# 1010-B1-solarwhat-light.net
KiCad netlist of a schematic drawn in EAGLE
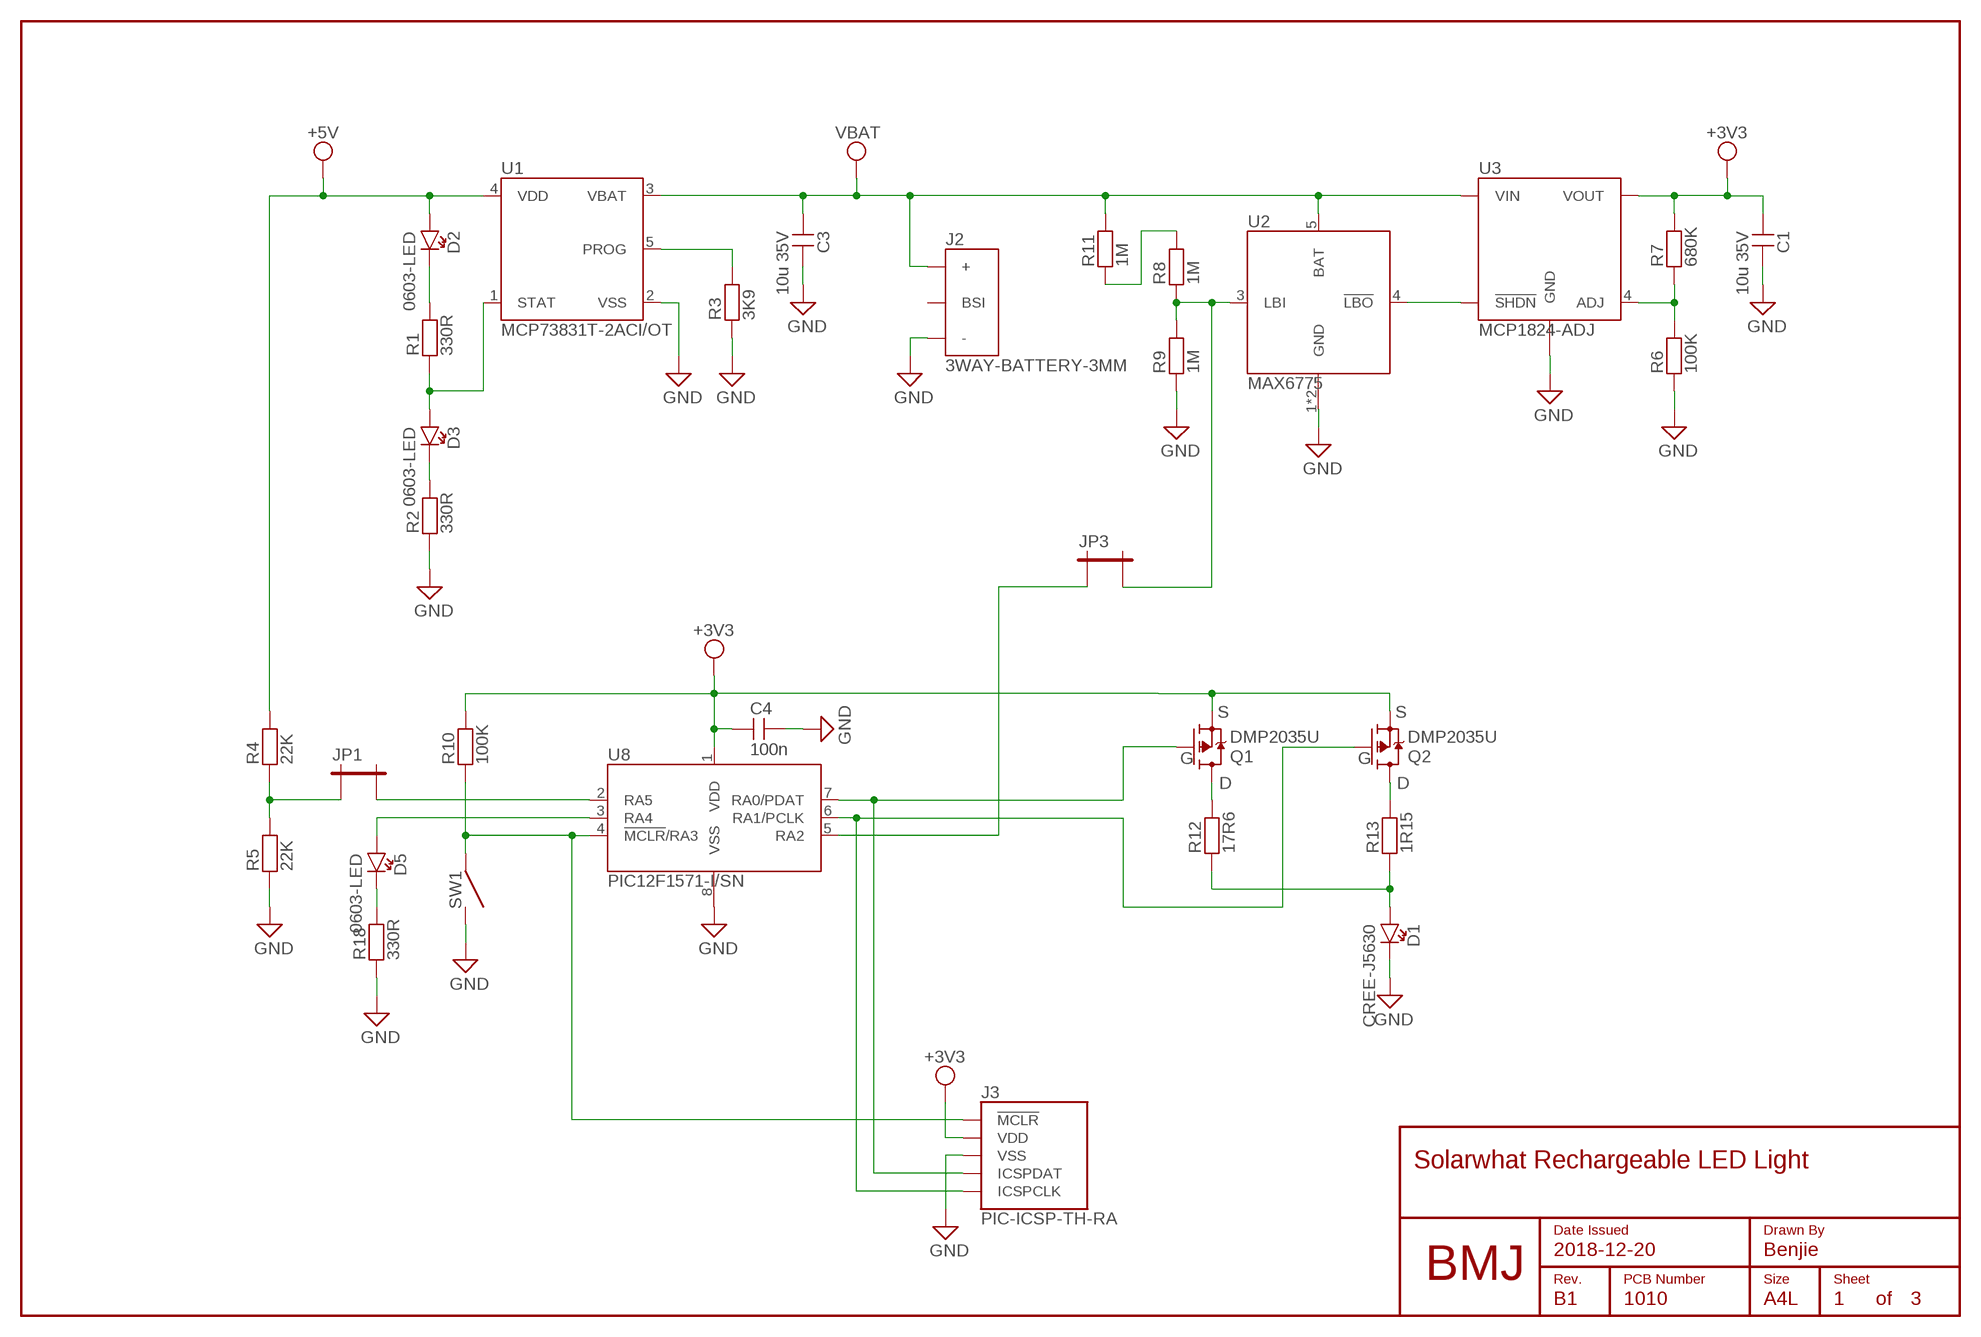
[diagram p0: schematic, sheet 1]
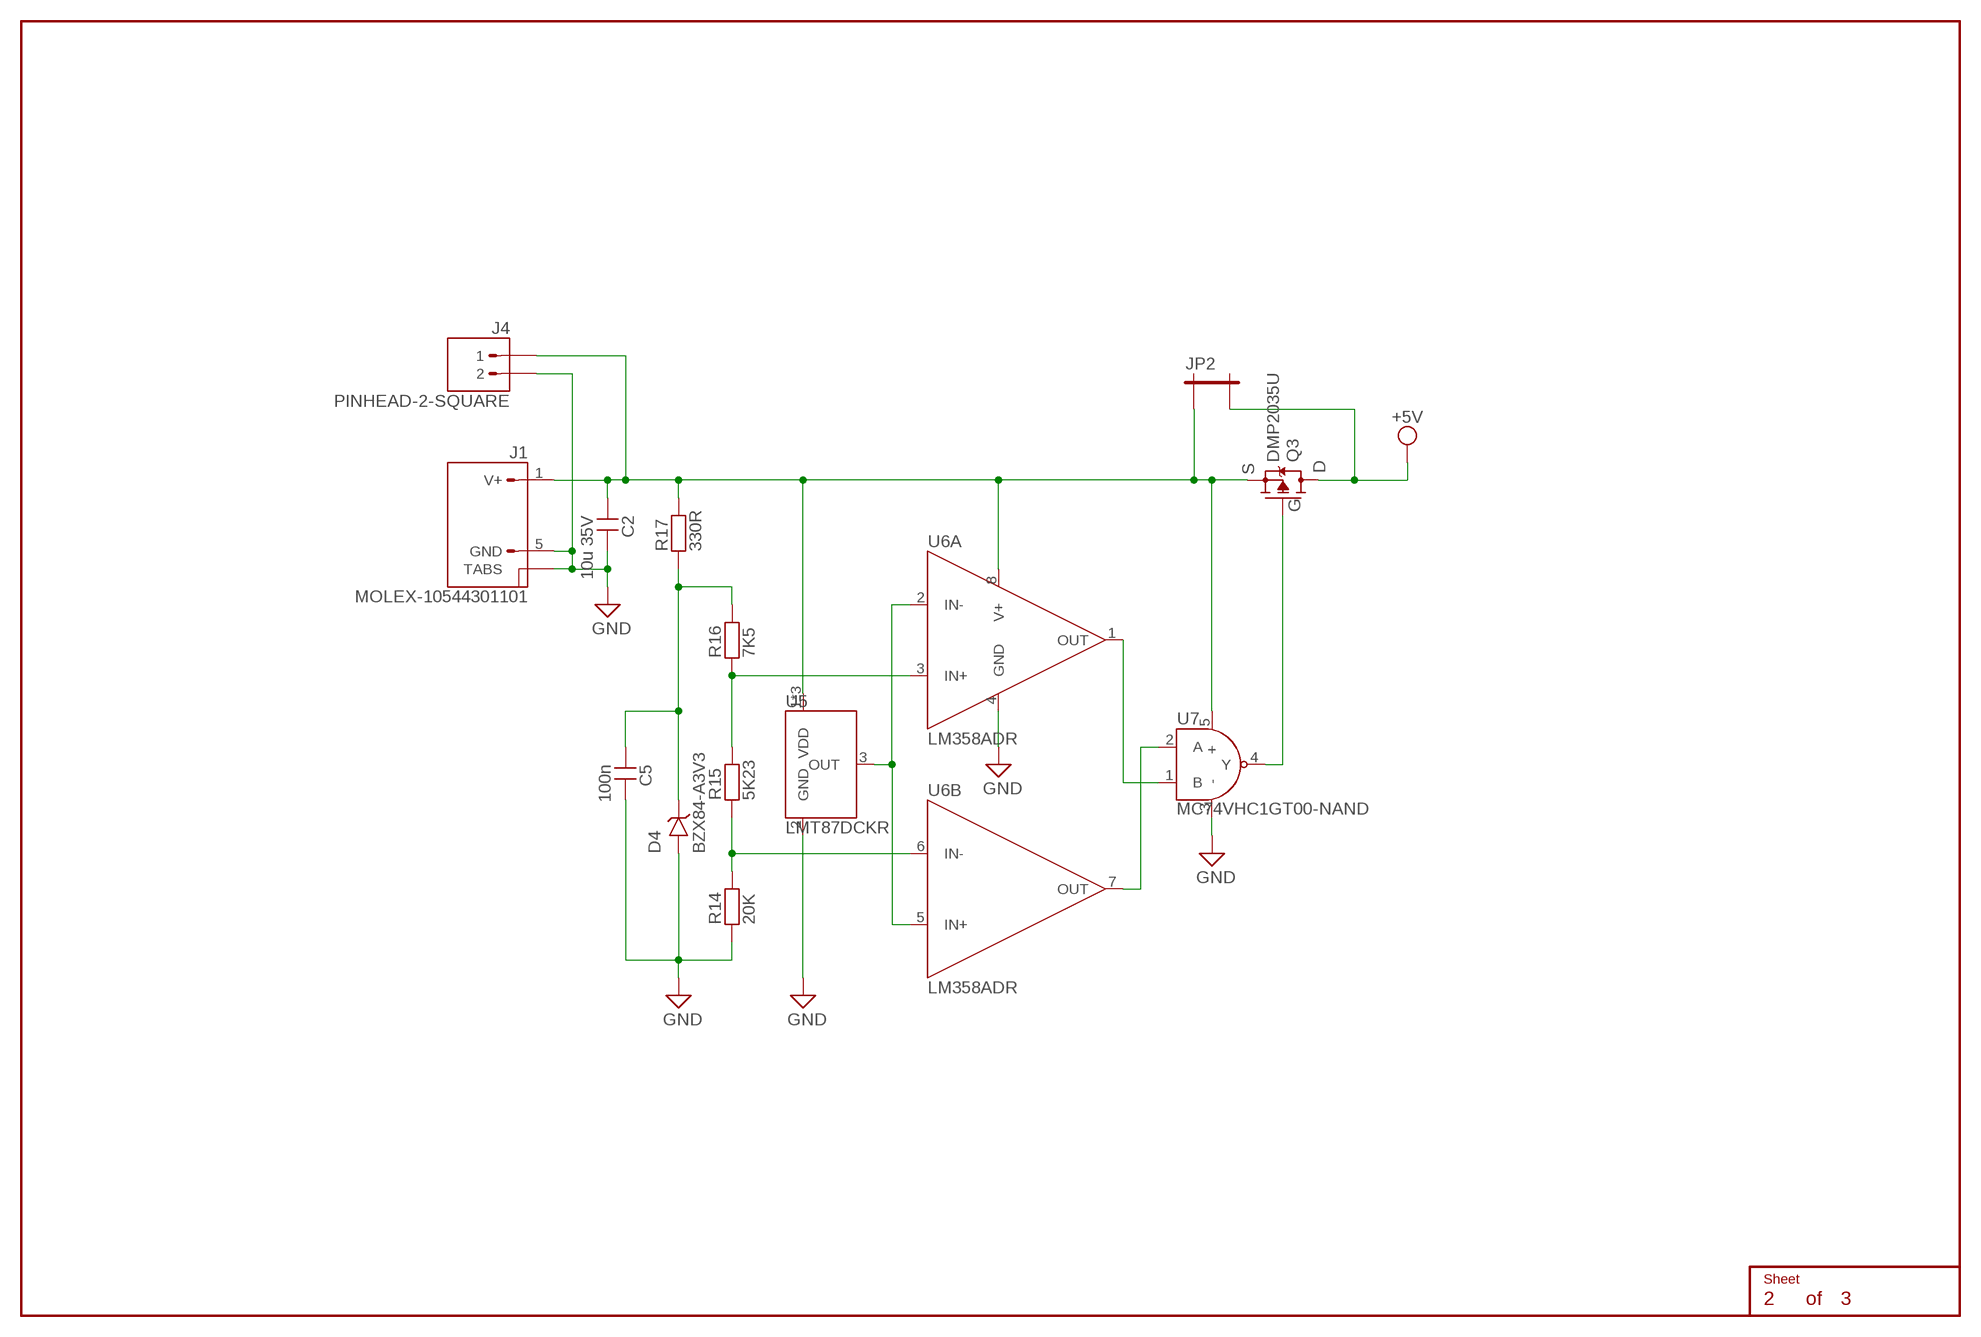
[diagram p1: schematic, sheet 2]
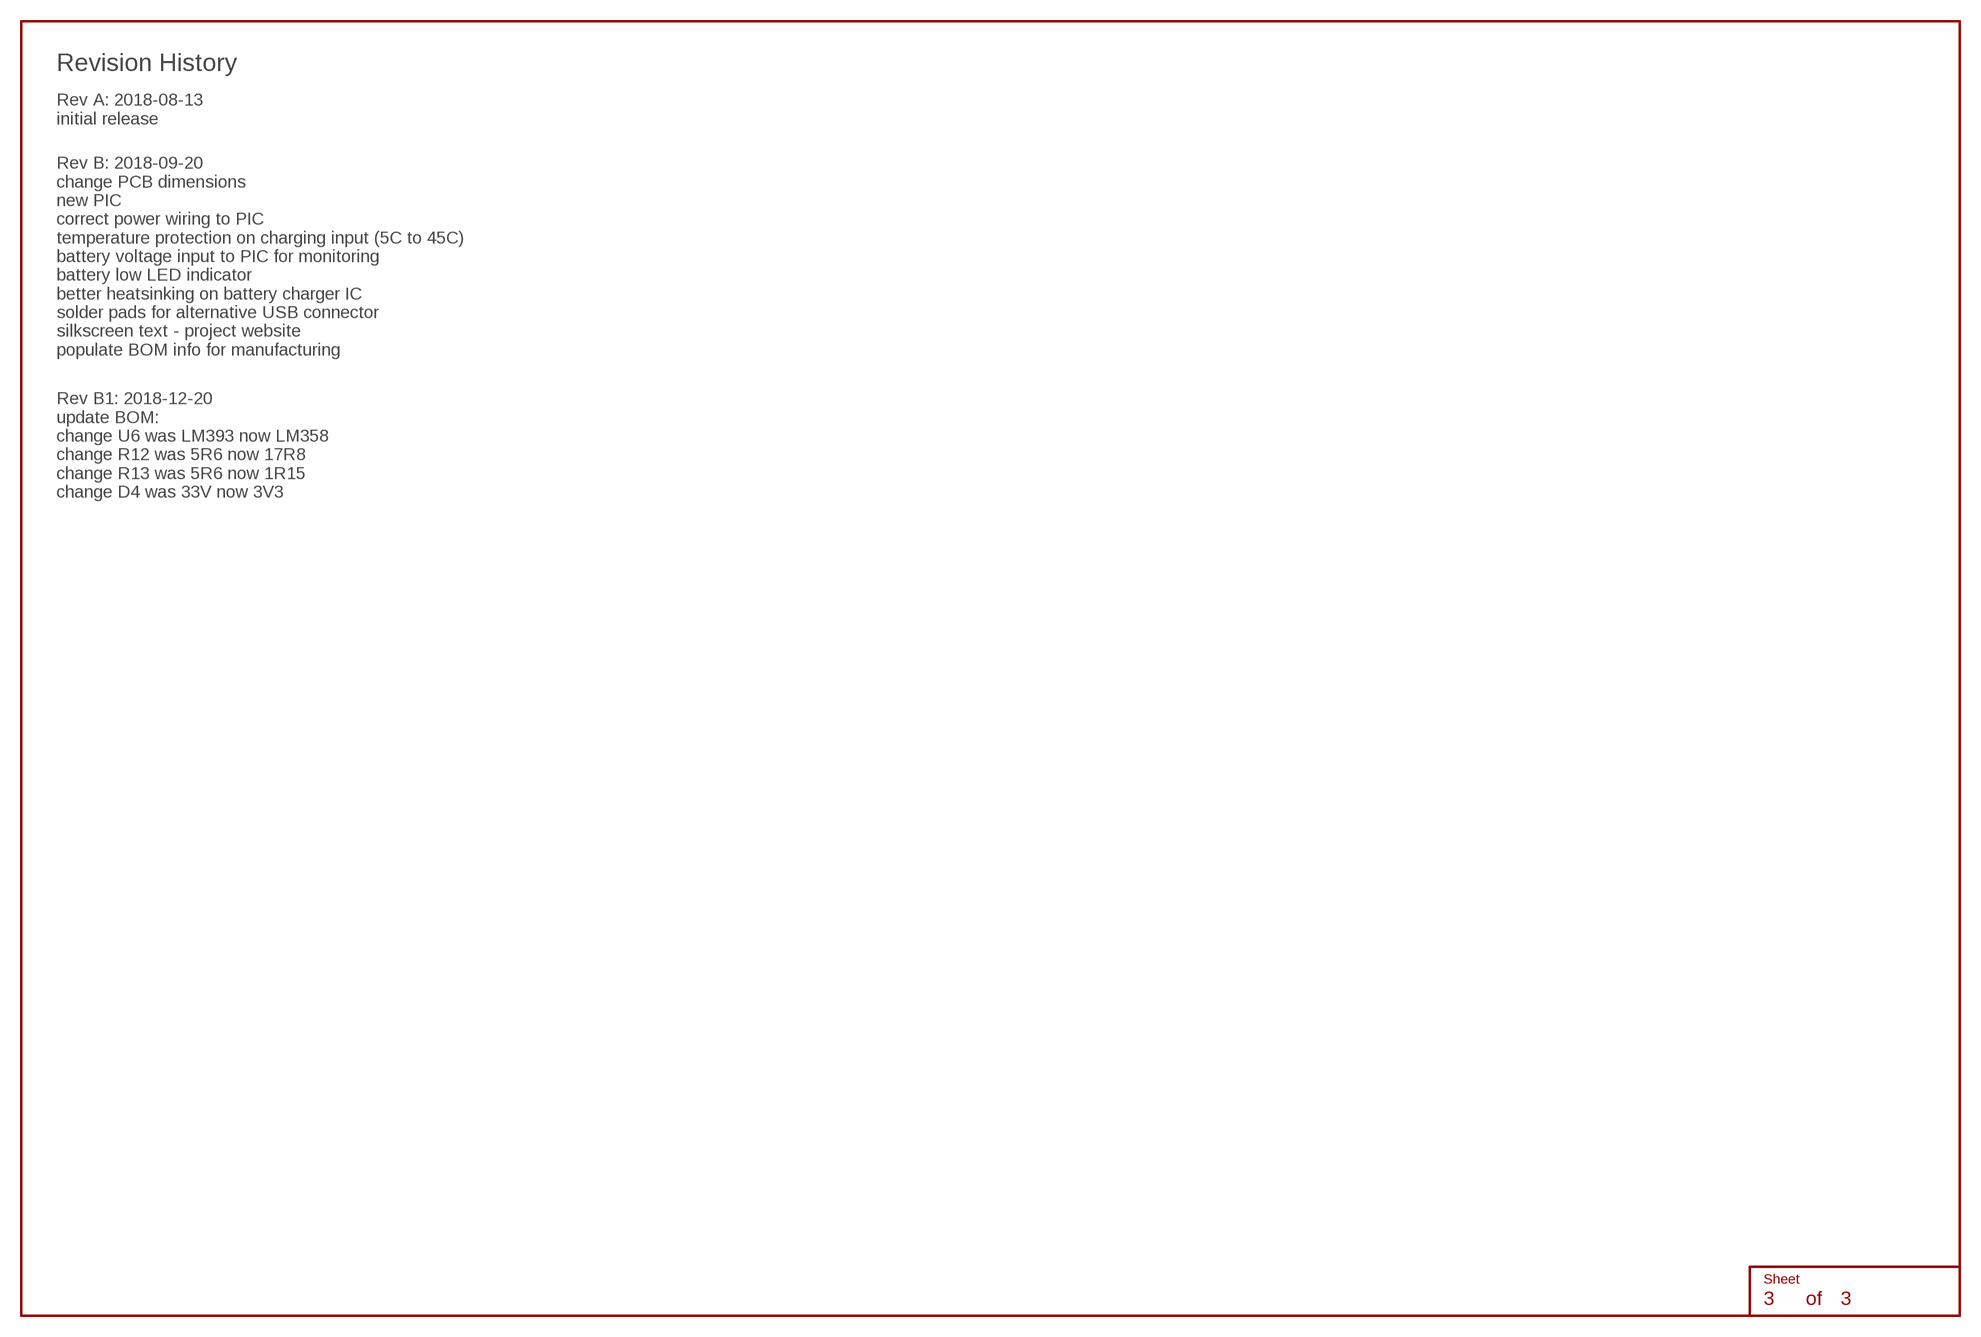
[diagram p2: schematic, sheet 3]

(export (version "E")
  (design (tool "Eeschema 10.0.6"))
  (components
    (comp (ref "C1")
      (value "10u 35V")
      (footprint "eagle-import:1206")
      (fields (field (name "MPN") "1206 10uF 35V 10% X7R"))
      (libsource (lib "eagle-import") (part "1206-10U-35V"))
    )
    (comp (ref "C3")
      (value "10u 35V")
      (footprint "eagle-import:1206")
      (fields (field (name "MPN") "1206 10uF 35V 10% X7R"))
      (libsource (lib "eagle-import") (part "1206-10U-35V"))
    )
    (comp (ref "C4")
      (value "100n")
      (footprint "eagle-import:0603")
      (fields (field (name "MPN") "0603 100nF 50V 10% X7R"))
      (libsource (lib "eagle-import") (part "0603-100N"))
    )
    (comp (ref "D1")
      (value "CREE-J5630")
      (footprint "eagle-import:CREE-J5630")
      (fields (field (name "MPN") "Cree JB5630AWT-C0-0000-000A0UC430E"))
      (libsource (lib "eagle-import") (part "CREE-J5630"))
    )
    (comp (ref "D2")
      (value "0603-LED")
      (footprint "eagle-import:0603-LED")
      (fields
        (field (name "MPN") "TruOpto OSR50603C1E")
        (field (name "MPN_1") "0603 orange")
        (field (name "SPN") "Farnell 2687484")
      )
      (libsource (lib "eagle-import") (part "0603-LED"))
    )
    (comp (ref "D3")
      (value "0603-LED")
      (footprint "eagle-import:0603-LED")
      (fields
        (field (name "MPN") "TruOpto OSR50603C1E")
        (field (name "MPN_1") "0603 green")
        (field (name "SPN") "Farnell 2687486")
      )
      (libsource (lib "eagle-import") (part "0603-LED"))
    )
    (comp (ref "D5")
      (value "0603-LED")
      (footprint "eagle-import:0603-LED")
      (fields
        (field (name "MPN") "TruOpto OSR50603C1E")
        (field (name "MPN_1") "0603 red")
        (field (name "SPN") "Farnell 2687488")
      )
      (libsource (lib "eagle-import") (part "0603-LED"))
    )
    (comp (ref "FRAME1")
      (value "A4L-NEW")
      (footprint "eagle-import:PCB-ID")
      (fields
        (field (name "DATEISSUED") "2018-12-20")
        (field (name "PCBNUMBER") "1010")
        (field (name "REVISION") "B1")
        (field (name "TITLE") "Solarwhat Rechargeable LED Light")
        (field (name "DRAWNBY") "Benjie")
      )
      (libsource (lib "eagle-import") (part "A4L-NEW"))
    )
    (comp (ref "J2")
      (value "3WAY-BATTERY-3MM")
      (footprint "eagle-import:3MM-BATTERY-3WAY")
      (fields (field (name "MPN") "AVX 009155003301006") (field (name "SPN") "Digi-key 478-4687-1-ND"))
      (libsource (lib "eagle-import") (part "3WAY-BATTERY-3MM"))
    )
    (comp (ref "J3")
      (value "PIC-ICSP-TH-RA")
      (footprint "eagle-import:PIC-ICSP-TH-RA")
      (libsource (lib "eagle-import") (part "PIC-ICSP-TH-RA"))
    )
    (comp (ref "JP1")
      (value "SOLDER-JUMPER-1MM-SQUARE")
      (footprint "eagle-import:SOLDER-JUMPER-1-1")
      (libsource (lib "eagle-import") (part "SOLDER-JUMPER-1MM-SQUARE"))
    )
    (comp (ref "JP3")
      (value "SOLDER-JUMPER-1MM-SQUARE")
      (footprint "eagle-import:SOLDER-JUMPER-1-1")
      (libsource (lib "eagle-import") (part "SOLDER-JUMPER-1MM-SQUARE"))
    )
    (comp (ref "LOGO1")
      (value "BMJ-LOGO")
      (footprint "eagle-import:BMJ-LOGO")
      (libsource (lib "eagle-import") (part "BMJ-LOGO"))
    )
    (comp (ref "Q1")
      (value "DMP2035U")
      (footprint "eagle-import:SOT-23")
      (fields (field (name "MPN") "Diodes Inc DMP2035U"))
      (libsource (lib "eagle-import") (part "DMP2035U"))
    )
    (comp (ref "Q2")
      (value "DMP2035U")
      (footprint "eagle-import:SOT-23")
      (fields (field (name "MPN") "Diodes Inc DMP2035U"))
      (libsource (lib "eagle-import") (part "DMP2035U"))
    )
    (comp (ref "R1")
      (value "330R")
      (footprint "eagle-import:0603")
      (fields (field (name "MPN") "0603 330R 1% 100mW"))
      (libsource (lib "eagle-import") (part "0603-1%-330R"))
    )
    (comp (ref "R2")
      (value "330R")
      (footprint "eagle-import:0603")
      (fields (field (name "MPN") "0603 330R 1% 100mW"))
      (libsource (lib "eagle-import") (part "0603-1%-330R"))
    )
    (comp (ref "R3")
      (value "3K9")
      (footprint "eagle-import:0603")
      (fields (field (name "MPN") "0603 3K9 1% 100mW"))
      (libsource (lib "eagle-import") (part "0603-1%-3K9"))
    )
    (comp (ref "R4")
      (value "22K")
      (footprint "eagle-import:0603")
      (fields (field (name "MPN") "0603 22K 1% 100mW"))
      (libsource (lib "eagle-import") (part "0603-1%-22K"))
    )
    (comp (ref "R5")
      (value "22K")
      (footprint "eagle-import:0603")
      (fields (field (name "MPN") "0603 22K 1% 100mW"))
      (libsource (lib "eagle-import") (part "0603-1%-22K"))
    )
    (comp (ref "R6")
      (value "100K")
      (footprint "eagle-import:0603")
      (fields (field (name "MPN") "0603 100K 1% 100mW"))
      (libsource (lib "eagle-import") (part "0603-1%-100K"))
    )
    (comp (ref "R7")
      (value "680K")
      (footprint "eagle-import:0603")
      (fields (field (name "MPN") "0603 680K 1% 100mW"))
      (libsource (lib "eagle-import") (part "0603-1%-680K"))
    )
    (comp (ref "R8")
      (value "1M")
      (footprint "eagle-import:0603")
      (fields (field (name "MPN") "0603 1M 1% 100mW"))
      (libsource (lib "eagle-import") (part "0603-1%-1M"))
    )
    (comp (ref "R9")
      (value "1M")
      (footprint "eagle-import:0603")
      (fields (field (name "MPN") "0603 1M 1% 100mW"))
      (libsource (lib "eagle-import") (part "0603-1%-1M"))
    )
    (comp (ref "R10")
      (value "100K")
      (footprint "eagle-import:0603")
      (fields (field (name "MPN") "0603 100K 1% 100mW"))
      (libsource (lib "eagle-import") (part "0603-1%-100K"))
    )
    (comp (ref "R11")
      (value "1M")
      (footprint "eagle-import:0603")
      (fields (field (name "MPN") "0603 1M 1% 100mW"))
      (libsource (lib "eagle-import") (part "0603-1%-1M"))
    )
    (comp (ref "R12")
      (value "17R6")
      (footprint "eagle-import:0805")
      (fields (field (name "MPN") "0805 17R8 1% 100mW"))
      (libsource (lib "eagle-import") (part "0805-1%-17R6"))
    )
    (comp (ref "R13")
      (value "1R15")
      (footprint "eagle-import:0805")
      (fields (field (name "MPN") "0805 1R15 1% 100mW"))
      (libsource (lib "eagle-import") (part "0805-1%-1R15"))
    )
    (comp (ref "R18")
      (value "330R")
      (footprint "eagle-import:0603")
      (fields (field (name "MPN") "0603 330R 1% 100mW"))
      (libsource (lib "eagle-import") (part "0603-1%-330R"))
    )
    (comp (ref "SW1")
      (value "ALCOSWITCH-FSM4JSMA")
      (footprint "eagle-import:ALCOSWITCH-FSM4JSMA")
      (fields (field (name "MPN") "Alcoswitch FSM4JSMA"))
      (libsource (lib "eagle-import") (part "ALCOSWITCH-FSM4JSMA"))
    )
    (comp (ref "U1")
      (value "MCP73831T-2ACI/OT")
      (footprint "eagle-import:SOT-23-5")
      (fields (field (name "MPN") "Microchip MCP73831T-2ACI/OT"))
      (libsource (lib "eagle-import") (part "MCP73831T-2ACI/OT"))
    )
    (comp (ref "U2")
      (value "MAX6775")
      (footprint "eagle-import:SC70")
      (fields (field (name "MPN") "Maxim MAX6775XKB+T") (field (name "SPN") "Farnell 2799268"))
      (libsource (lib "eagle-import") (part "MAX6775"))
    )
    (comp (ref "U3")
      (value "MCP1824-ADJ")
      (footprint "eagle-import:SOT-23-5")
      (fields (field (name "MPN") "Microchip MCP1824T-ADJE/OT") (field (name "SPN") "Farnell 1578393"))
      (libsource (lib "eagle-import") (part "MCP1824-ADJ"))
    )
    (comp (ref "U8")
      (value "PIC12F1571-I/SN")
      (footprint "eagle-import:SOIC-8")
      (fields (field (name "MPN") "Microchip PIC12F1571-I/SN"))
      (libsource (lib "eagle-import") (part "PIC12F1571-I/SN"))
    )
    (comp (ref "C2")
      (value "10u 35V")
      (footprint "eagle-import:1206")
      (fields (field (name "MPN") "1206 10uF 35V 10% X7R"))
      (libsource (lib "eagle-import") (part "1206-10U-35V"))
    )
    (comp (ref "C5")
      (value "100n")
      (footprint "eagle-import:0603")
      (fields (field (name "MPN") "0603 100nF 50V 10% X7R"))
      (libsource (lib "eagle-import") (part "0603-100N"))
    )
    (comp (ref "D4")
      (value "BZX84-A3V3")
      (footprint "eagle-import:SOT-23")
      (fields (field (name "MPN") "Nexperia BZX84-A3V3"))
      (libsource (lib "eagle-import") (part "BZX84-A3V3"))
    )
    (comp (ref "FRAME2")
      (value "A4L-CONTINUATION")
      (footprint "eagle-import:EMPTY")
      (libsource (lib "eagle-import") (part "A4L-CONTINUATION"))
    )
    (comp (ref "J1")
      (value "MOLEX-10544301101")
      (footprint "eagle-import:MOLEX-105443-1101-POWERONLY")
      (fields (field (name "MPN") "Molex 10544301-1101"))
      (libsource (lib "eagle-import") (part "MOLEX-10544301101-POWERONLY"))
    )
    (comp (ref "J4")
      (value "PINHEAD-2-SQUARE")
      (footprint "eagle-import:PINHEAD-2-SQUARE")
      (libsource (lib "eagle-import") (part "PINHEAD-2-SQUARE"))
    )
    (comp (ref "JP2")
      (value "SOLDER-JUMPER-1MM-SQUARE")
      (footprint "eagle-import:SOLDER-JUMPER-1-1")
      (libsource (lib "eagle-import") (part "SOLDER-JUMPER-1MM-SQUARE"))
    )
    (comp (ref "Q3")
      (value "DMP2035U")
      (footprint "eagle-import:SOT-23")
      (fields (field (name "MPN") "Diodes Inc DMP2035U"))
      (libsource (lib "eagle-import") (part "DMP2035U"))
    )
    (comp (ref "R14")
      (value "20K")
      (footprint "eagle-import:0603")
      (fields (field (name "MPN") "0603 20K 1% 100mW"))
      (libsource (lib "eagle-import") (part "0603-1%-20K"))
    )
    (comp (ref "R15")
      (value "5K23")
      (footprint "eagle-import:0603")
      (fields (field (name "MPN") "0603 5K23 1% 100mW"))
      (libsource (lib "eagle-import") (part "0603-1%-5K23"))
    )
    (comp (ref "R16")
      (value "7K5")
      (footprint "eagle-import:0603")
      (fields (field (name "MPN") "0603 7K5 1% 100mW"))
      (libsource (lib "eagle-import") (part "0603-1%-7K5"))
    )
    (comp (ref "R17")
      (value "330R")
      (footprint "eagle-import:0603")
      (fields (field (name "MPN") "0603 330R 1% 100mW"))
      (libsource (lib "eagle-import") (part "0603-1%-330R"))
    )
    (comp (ref "U5")
      (value "LMT87DCKR")
      (footprint "eagle-import:SC70")
      (fields (field (name "MPN") "TI LMT87DCKR"))
      (libsource (lib "eagle-import") (part "LMT87DCKR"))
    )
    (comp (ref "U6")
      (value "LM358ADR")
      (footprint "eagle-import:SOIC-8")
      (fields (field (name "MPN") "TI LM358ADR"))
      (libsource (lib "eagle-import") (part "LM358ADR"))
    )
    (comp (ref "U7")
      (value "MC74VHC1GT00-NAND")
      (footprint "eagle-import:SC70")
      (fields (field (name "MPN") "On Semi MC74VHC1GT00DF"))
      (libsource (lib "eagle-import") (part "MC74VHC1GT00-NAND"))
    )
    (comp (ref "FRAME3")
      (value "A4L-CONTINUATION")
      (footprint "eagle-import:EMPTY")
      (libsource (lib "eagle-import") (part "A4L-CONTINUATION"))
    )
  )
  (nets
    (net (code "1") (name "+3V3") (class "Default")
      (node (ref "C1") (pin "1") (pinfunction "1_1") (pintype "passive"))
      (node (ref "C4") (pin "1") (pinfunction "1_1") (pintype "passive"))
      (node (ref "J3") (pin "2") (pinfunction "VDD_2") (pintype "power_in"))
      (node (ref "Q1") (pin "2") (pinfunction "S_2") (pintype "passive"))
      (node (ref "Q2") (pin "2") (pinfunction "S_2") (pintype "passive"))
      (node (ref "R10") (pin "2") (pinfunction "2_2") (pintype "passive"))
      (node (ref "R7") (pin "2") (pinfunction "2_2") (pintype "passive"))
      (node (ref "U3") (pin "5") (pinfunction "VOUT_5") (pintype "bidirectional"))
      (node (ref "U8") (pin "1") (pinfunction "VDD_1") (pintype "power_in"))
    )
    (net (code "2") (name "+5V") (class "Default")
      (node (ref "D2") (pin "A") (pinfunction "A_A") (pintype "passive"))
      (node (ref "JP2") (pin "2") (pinfunction "2_2") (pintype "passive"))
      (node (ref "Q3") (pin "3") (pinfunction "D_3") (pintype "passive"))
      (node (ref "R4") (pin "2") (pinfunction "2_2") (pintype "passive"))
      (node (ref "U1") (pin "4") (pinfunction "VDD_4") (pintype "bidirectional"))
    )
    (net (code "3") (name "GND") (class "Default")
      (node (ref "C1") (pin "2") (pinfunction "2_2") (pintype "passive"))
      (node (ref "C2") (pin "2") (pinfunction "2_2") (pintype "passive"))
      (node (ref "C3") (pin "2") (pinfunction "2_2") (pintype "passive"))
      (node (ref "C4") (pin "2") (pinfunction "2_2") (pintype "passive"))
      (node (ref "C5") (pin "2") (pinfunction "2_2") (pintype "passive"))
      (node (ref "D1") (pin "K") (pinfunction "C_K") (pintype "passive"))
      (node (ref "D4") (pin "1") (pinfunction "A_1") (pintype "passive"))
      (node (ref "J1") (pin "5") (pinfunction "GND_5") (pintype "passive"))
      (node (ref "J1") (pin "GND@1") (pinfunction "TABS_GND@1") (pintype "passive"))
      (node (ref "J1") (pin "GND@2") (pinfunction "TABS_GND@2") (pintype "passive"))
      (node (ref "J1") (pin "GND@3") (pinfunction "TABS_GND@3") (pintype "passive"))
      (node (ref "J1") (pin "GND@4") (pinfunction "TABS_GND@4") (pintype "passive"))
      (node (ref "J1") (pin "GND@5") (pinfunction "TABS_GND@5") (pintype "passive"))
      (node (ref "J1") (pin "GND@6") (pinfunction "TABS_GND@6") (pintype "passive"))
      (node (ref "J2") (pin "-") (pinfunction "-_-") (pintype "bidirectional"))
      (node (ref "J3") (pin "3") (pinfunction "VSS_3") (pintype "power_in"))
      (node (ref "J4") (pin "2") (pinfunction "2_2") (pintype "passive"))
      (node (ref "R14") (pin "1") (pinfunction "1_1") (pintype "passive"))
      (node (ref "R18") (pin "1") (pinfunction "1_1") (pintype "passive"))
      (node (ref "R2") (pin "1") (pinfunction "1_1") (pintype "passive"))
      (node (ref "R3") (pin "1") (pinfunction "1_1") (pintype "passive"))
      (node (ref "R5") (pin "1") (pinfunction "1_1") (pintype "passive"))
      (node (ref "R6") (pin "1") (pinfunction "1_1") (pintype "passive"))
      (node (ref "R9") (pin "1") (pinfunction "1_1") (pintype "passive"))
      (node (ref "SW1") (pin "2@1") (pinfunction "NO_2@1") (pintype "passive"))
      (node (ref "SW1") (pin "2@2") (pinfunction "NO_2@2") (pintype "passive"))
      (node (ref "U1") (pin "2") (pinfunction "VSS_2") (pintype "bidirectional"))
      (node (ref "U2") (pin "1") (pinfunction "GND_1") (pintype "bidirectional"))
      (node (ref "U2") (pin "2") (pinfunction "GND_2") (pintype "bidirectional"))
      (node (ref "U3") (pin "2") (pinfunction "GND_2") (pintype "bidirectional"))
      (node (ref "U5") (pin "2") (pinfunction "GND_2") (pintype "bidirectional"))
      (node (ref "U6") (pin "4") (pinfunction "GND_4") (pintype "power_in"))
      (node (ref "U7") (pin "3") (pinfunction "-_3") (pintype "passive"))
      (node (ref "U8") (pin "8") (pinfunction "VSS_8") (pintype "power_in"))
    )
    (net (code "4") (name "Net-(D1-PadA)") (class "Default")
      (node (ref "D1") (pin "A") (pinfunction "A_A") (pintype "passive"))
      (node (ref "R12") (pin "1") (pinfunction "1_1") (pintype "passive"))
      (node (ref "R13") (pin "1") (pinfunction "1_1") (pintype "passive"))
    )
    (net (code "5") (name "Net-(D2-PadC)") (class "Default")
      (node (ref "D2") (pin "C") (pinfunction "C_C") (pintype "passive"))
      (node (ref "R1") (pin "2") (pinfunction "2_2") (pintype "passive"))
    )
    (net (code "6") (name "Net-(D3-PadC)") (class "Default")
      (node (ref "D3") (pin "C") (pinfunction "C_C") (pintype "passive"))
      (node (ref "R2") (pin "2") (pinfunction "2_2") (pintype "passive"))
    )
    (net (code "7") (name "Net-(D4-K)") (class "Default")
      (node (ref "C5") (pin "1") (pinfunction "1_1") (pintype "passive"))
      (node (ref "D4") (pin "3") (pinfunction "K_3") (pintype "passive"))
      (node (ref "R16") (pin "2") (pinfunction "2_2") (pintype "passive"))
      (node (ref "R17") (pin "1") (pinfunction "1_1") (pintype "passive"))
    )
    (net (code "8") (name "Net-(D5-PadC)") (class "Default")
      (node (ref "D5") (pin "C") (pinfunction "C_C") (pintype "passive"))
      (node (ref "R18") (pin "2") (pinfunction "2_2") (pintype "passive"))
    )
    (net (code "9") (name "Net-(J1-V+)") (class "Default")
      (node (ref "C2") (pin "1") (pinfunction "1_1") (pintype "passive"))
      (node (ref "J1") (pin "1") (pinfunction "V+_1") (pintype "passive"))
      (node (ref "J4") (pin "1") (pinfunction "1_1") (pintype "passive"))
      (node (ref "JP2") (pin "1") (pinfunction "1_1") (pintype "passive"))
      (node (ref "Q3") (pin "2") (pinfunction "S_2") (pintype "passive"))
      (node (ref "R17") (pin "2") (pinfunction "2_2") (pintype "passive"))
      (node (ref "U5") (pin "1") (pinfunction "VDD_1") (pintype "bidirectional"))
      (node (ref "U5") (pin "4") (pinfunction "VDD_4") (pintype "bidirectional"))
      (node (ref "U5") (pin "5") (pinfunction "VDD_5") (pintype "bidirectional"))
      (node (ref "U6") (pin "8") (pinfunction "V+_8") (pintype "power_in"))
      (node (ref "U7") (pin "5") (pinfunction "+_5") (pintype "power_in"))
    )
    (net (code "10") (name "Net-(J3-ICSPCLK)") (class "Default")
      (node (ref "J3") (pin "5") (pinfunction "ICSPCLK_5") (pintype "passive"))
      (node (ref "Q2") (pin "1") (pinfunction "G_1") (pintype "passive"))
      (node (ref "U8") (pin "6") (pinfunction "RA1/PCLK_6") (pintype "bidirectional"))
    )
    (net (code "11") (name "Net-(J3-ICSPDAT)") (class "Default")
      (node (ref "J3") (pin "4") (pinfunction "ICSPDAT_4") (pintype "passive"))
      (node (ref "Q1") (pin "1") (pinfunction "G_1") (pintype "passive"))
      (node (ref "U8") (pin "7") (pinfunction "RA0/PDAT_7") (pintype "bidirectional"))
    )
    (net (code "12") (name "Net-(J3-~{MCLR})") (class "Default")
      (node (ref "J3") (pin "1") (pinfunction "~{MCLR}_1") (pintype "passive"))
      (node (ref "R10") (pin "1") (pinfunction "1_1") (pintype "passive"))
      (node (ref "SW1") (pin "1@1") (pinfunction "COM_1@1") (pintype "passive"))
      (node (ref "SW1") (pin "1@2") (pinfunction "COM_1@2") (pintype "passive"))
      (node (ref "U8") (pin "4") (pinfunction "~{MCLR}/RA3_4") (pintype "bidirectional"))
    )
    (net (code "13") (name "Net-(JP1-Pad1)") (class "Default")
      (node (ref "JP1") (pin "1") (pinfunction "1_1") (pintype "passive"))
      (node (ref "R4") (pin "1") (pinfunction "1_1") (pintype "passive"))
      (node (ref "R5") (pin "2") (pinfunction "2_2") (pintype "passive"))
    )
    (net (code "14") (name "Net-(Q1-D)") (class "Default")
      (node (ref "Q1") (pin "3") (pinfunction "D_3") (pintype "passive"))
      (node (ref "R12") (pin "2") (pinfunction "2_2") (pintype "passive"))
    )
    (net (code "15") (name "Net-(Q2-D)") (class "Default")
      (node (ref "Q2") (pin "3") (pinfunction "D_3") (pintype "passive"))
      (node (ref "R13") (pin "2") (pinfunction "2_2") (pintype "passive"))
    )
    (net (code "16") (name "Net-(Q3-G)") (class "Default")
      (node (ref "Q3") (pin "1") (pinfunction "G_1") (pintype "passive"))
      (node (ref "U7") (pin "4") (pinfunction "Y_4") (pintype "output"))
    )
    (net (code "17") (name "Net-(R11-Pad1)") (class "Default")
      (node (ref "R11") (pin "1") (pinfunction "1_1") (pintype "passive"))
      (node (ref "R8") (pin "2") (pinfunction "2_2") (pintype "passive"))
    )
    (net (code "18") (name "Net-(U1-PROG)") (class "Default")
      (node (ref "R3") (pin "2") (pinfunction "2_2") (pintype "passive"))
      (node (ref "U1") (pin "5") (pinfunction "PROG_5") (pintype "bidirectional"))
    )
    (net (code "19") (name "Net-(U1-STAT)") (class "Default")
      (node (ref "D3") (pin "A") (pinfunction "A_A") (pintype "passive"))
      (node (ref "R1") (pin "1") (pinfunction "1_1") (pintype "passive"))
      (node (ref "U1") (pin "1") (pinfunction "STAT_1") (pintype "bidirectional"))
    )
    (net (code "20") (name "Net-(U2-LBI)") (class "Default")
      (node (ref "JP3") (pin "2") (pinfunction "2_2") (pintype "passive"))
      (node (ref "R8") (pin "1") (pinfunction "1_1") (pintype "passive"))
      (node (ref "R9") (pin "2") (pinfunction "2_2") (pintype "passive"))
      (node (ref "U2") (pin "3") (pinfunction "LBI_3") (pintype "bidirectional"))
    )
    (net (code "21") (name "Net-(U2-~{LBO})") (class "Default")
      (node (ref "U2") (pin "4") (pinfunction "~{LBO}_4") (pintype "bidirectional"))
      (node (ref "U3") (pin "3") (pinfunction "~{SHDN}_3") (pintype "bidirectional"))
    )
    (net (code "22") (name "Net-(U3-ADJ)") (class "Default")
      (node (ref "R6") (pin "2") (pinfunction "2_2") (pintype "passive"))
      (node (ref "R7") (pin "1") (pinfunction "1_1") (pintype "passive"))
      (node (ref "U3") (pin "4") (pinfunction "ADJ_4") (pintype "bidirectional"))
    )
    (net (code "23") (name "Net-(U5-OUT)") (class "Default")
      (node (ref "U5") (pin "3") (pinfunction "OUT_3") (pintype "bidirectional"))
      (node (ref "U6") (pin "2") (pinfunction "IN-_2") (pintype "input"))
      (node (ref "U6") (pin "5") (pinfunction "IN+_5") (pintype "input"))
    )
    (net (code "24") (name "Net-(U6A-IN+)") (class "Default")
      (node (ref "R15") (pin "2") (pinfunction "2_2") (pintype "passive"))
      (node (ref "R16") (pin "1") (pinfunction "1_1") (pintype "passive"))
      (node (ref "U6") (pin "3") (pinfunction "IN+_3") (pintype "input"))
    )
    (net (code "25") (name "Net-(U6A-OUT)") (class "Default")
      (node (ref "U6") (pin "1") (pinfunction "OUT_1") (pintype "output"))
      (node (ref "U7") (pin "1") (pinfunction "B_1") (pintype "input"))
    )
    (net (code "26") (name "Net-(U6B-IN-)") (class "Default")
      (node (ref "R14") (pin "2") (pinfunction "2_2") (pintype "passive"))
      (node (ref "R15") (pin "1") (pinfunction "1_1") (pintype "passive"))
      (node (ref "U6") (pin "6") (pinfunction "IN-_6") (pintype "input"))
    )
    (net (code "27") (name "Net-(U6B-OUT)") (class "Default")
      (node (ref "U6") (pin "7") (pinfunction "OUT_7") (pintype "output"))
      (node (ref "U7") (pin "2") (pinfunction "A_2") (pintype "input"))
    )
    (net (code "28") (name "Net-(U8-RA2)") (class "Default")
      (node (ref "JP3") (pin "1") (pinfunction "1_1") (pintype "passive"))
      (node (ref "U8") (pin "5") (pinfunction "RA2_5") (pintype "bidirectional"))
    )
    (net (code "29") (name "Net-(U8-RA4)") (class "Default")
      (node (ref "D5") (pin "A") (pinfunction "A_A") (pintype "passive"))
      (node (ref "U8") (pin "3") (pinfunction "RA4_3") (pintype "bidirectional"))
    )
    (net (code "30") (name "Net-(U8-RA5)") (class "Default")
      (node (ref "JP1") (pin "2") (pinfunction "2_2") (pintype "passive"))
      (node (ref "U8") (pin "2") (pinfunction "RA5_2") (pintype "bidirectional"))
    )
    (net (code "31") (name "VBAT") (class "Default")
      (node (ref "C3") (pin "1") (pinfunction "1_1") (pintype "passive"))
      (node (ref "J2") (pin "+") (pinfunction "+_+") (pintype "bidirectional"))
      (node (ref "R11") (pin "2") (pinfunction "2_2") (pintype "passive"))
      (node (ref "U1") (pin "3") (pinfunction "VBAT_3") (pintype "bidirectional"))
      (node (ref "U2") (pin "5") (pinfunction "BAT_5") (pintype "bidirectional"))
      (node (ref "U3") (pin "1") (pinfunction "VIN_1") (pintype "bidirectional"))
    )
    (net (code "32") (name "unconnected-(J2-PadBSI)") (class "Default")
      (node (ref "J2") (pin "BSI") (pinfunction "BSI_BSI") (pintype "bidirectional"))
    )
  )
)
